# connectors.net
KiCad netlist of a schematic drawn in Altium Designer
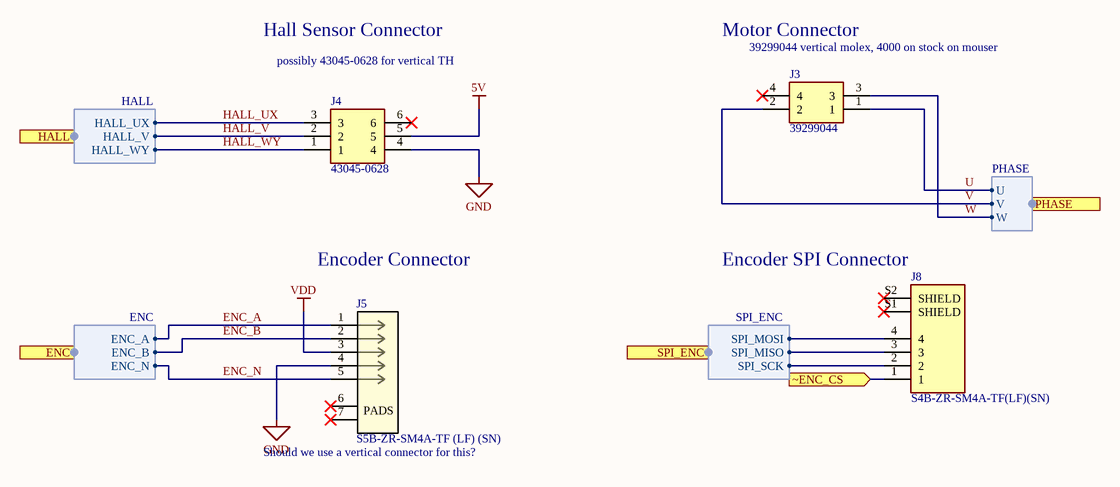
[diagram p0: connectors.SchDoc]

(export (version "E")
  (design (tool "Eeschema 10.0.6"))
  (components
    (comp (ref "J3")
      (value "39299044")
      (footprint "39299044")
      (description "Molex 39299044 4POS Minifit\r\ndual row, vertical")
      (fields (field (name "PART NUMBER") "CN HDR 4POS Molex 39299044 VERT"))
      (libsource (lib "Connector_Library") (part "CN HDR 4POS Molex 39299044 VERT"))
    )
    (comp (ref "J4")
      (value "43045-0628")
      (footprint "430450628")
      (description "Molex 43045-0628 6POS Microfit\r\ndual row, Vertical")
      (fields (field (name "PART NUMBER") "CN HDR 6POS Molex 43045-0628"))
      (libsource (lib "Connector_Library") (part "CN HDR 6POS Molex 43045-0628"))
    )
    (comp (ref "J5")
      (value "S5B-ZR-SM4A-TF (LF) (SN)")
      (footprint "JST_S5B-ZR-SM4A-TF")
      (description "Connector Header Surface Mount, Right Angle 5 position 0.059\" (1.50mm)")
      (fields (field (name "PART NUMBER") "CN 5POS JST ZR RA"))
      (libsource (lib "Connector_Library") (part "CN 5POS JST ZR RA"))
    )
    (comp (ref "J8")
      (value "S4B-ZR-SM4A-TF(LF)(SN)")
      (footprint "CN HDR 4POS SMD JST ZR")
      (description "Connector Header Surface Mount, Right Angle 4 position 0.059 (1.50mm)")
      (fields (field (name "MF") "JST Sales") (field (name "PART NUMBER") "CN HDR 4POS SMD JST ZR"))
      (libsource (lib "Connector_Library") (part "CN HDR 4POS SMD JST ZR"))
    )
  )
  (nets
    (net (code "5") (name "/ENC_A") (class "Default")
      (node (ref "J5") (pin "1") (pinfunction "1_1") (pintype "passive"))
    )
    (net (code "6") (name "/ENC_B") (class "Default")
      (node (ref "J5") (pin "2") (pinfunction "2_2") (pintype "passive"))
    )
    (net (code "7") (name "/ENC_N") (class "Default")
      (node (ref "J5") (pin "5") (pinfunction "5_5") (pintype "passive"))
    )
    (net (code "8") (name "/HALL_UX") (class "Default")
      (node (ref "J4") (pin "3") (pinfunction "3_3") (pintype "passive"))
    )
    (net (code "9") (name "/HALL_V") (class "Default")
      (node (ref "J4") (pin "2") (pinfunction "2_2") (pintype "passive"))
    )
    (net (code "10") (name "/HALL_WY") (class "Default")
      (node (ref "J4") (pin "1") (pinfunction "1_1") (pintype "passive"))
    )
    (net (code "11") (name "/SPI_MISO") (class "Default")
      (node (ref "J8") (pin "3") (pinfunction "3_3") (pintype "passive"))
    )
    (net (code "12") (name "/SPI_MOSI") (class "Default")
      (node (ref "J8") (pin "4") (pinfunction "4_4") (pintype "passive"))
    )
    (net (code "13") (name "/SPI_SCK") (class "Default")
      (node (ref "J8") (pin "2") (pinfunction "2_2") (pintype "passive"))
    )
    (net (code "14") (name "/U") (class "Default")
      (node (ref "J3") (pin "1") (pinfunction "1_1") (pintype "passive"))
    )
    (net (code "15") (name "/V") (class "Default")
      (node (ref "J3") (pin "2") (pinfunction "2_2") (pintype "passive"))
    )
    (net (code "16") (name "/W") (class "Default")
      (node (ref "J3") (pin "3") (pinfunction "3_3") (pintype "passive"))
    )
    (net (code "21") (name "/~ENC_CS") (class "Default")
      (node (ref "J8") (pin "1") (pinfunction "1_1") (pintype "passive"))
    )
    (net (code "22") (name "5V") (class "Default")
      (node (ref "J4") (pin "5") (pinfunction "5_5") (pintype "passive"))
    )
    (net (code "23") (name "GND") (class "Default")
      (node (ref "J4") (pin "4") (pinfunction "4_4") (pintype "passive"))
      (node (ref "J5") (pin "4") (pinfunction "4_4") (pintype "passive"))
    )
    (net (code "24") (name "VDD") (class "Default")
      (node (ref "J5") (pin "3") (pinfunction "3_3") (pintype "passive"))
    )
    (net (code "25") (name "unconnected-(J3-Pad4)") (class "Default")
      (node (ref "J3") (pin "4") (pinfunction "4_4") (pintype "passive+no_connect"))
    )
    (net (code "26") (name "unconnected-(J4-Pad6)") (class "Default")
      (node (ref "J4") (pin "6") (pinfunction "6_6") (pintype "passive+no_connect"))
    )
    (net (code "27") (name "unconnected-(J5-Pad6)") (class "Default")
      (node (ref "J5") (pin "6") (pinfunction "6_6") (pintype "passive+no_connect"))
    )
    (net (code "28") (name "unconnected-(J5-Pad7)") (class "Default")
      (node (ref "J5") (pin "7") (pinfunction "7_7") (pintype "passive+no_connect"))
    )
    (net (code "29") (name "unconnected-(J8-SHIELD-PadS1)") (class "Default")
      (node (ref "J8") (pin "S1") (pinfunction "SHIELD_S1") (pintype "passive+no_connect"))
    )
    (net (code "30") (name "unconnected-(J8-SHIELD-PadS2)") (class "Default")
      (node (ref "J8") (pin "S2") (pinfunction "SHIELD_S2") (pintype "passive+no_connect"))
    )
  )
)
